# Schematic_st500E.net
KiCad netlist of a schematic drawn in Altium Designer
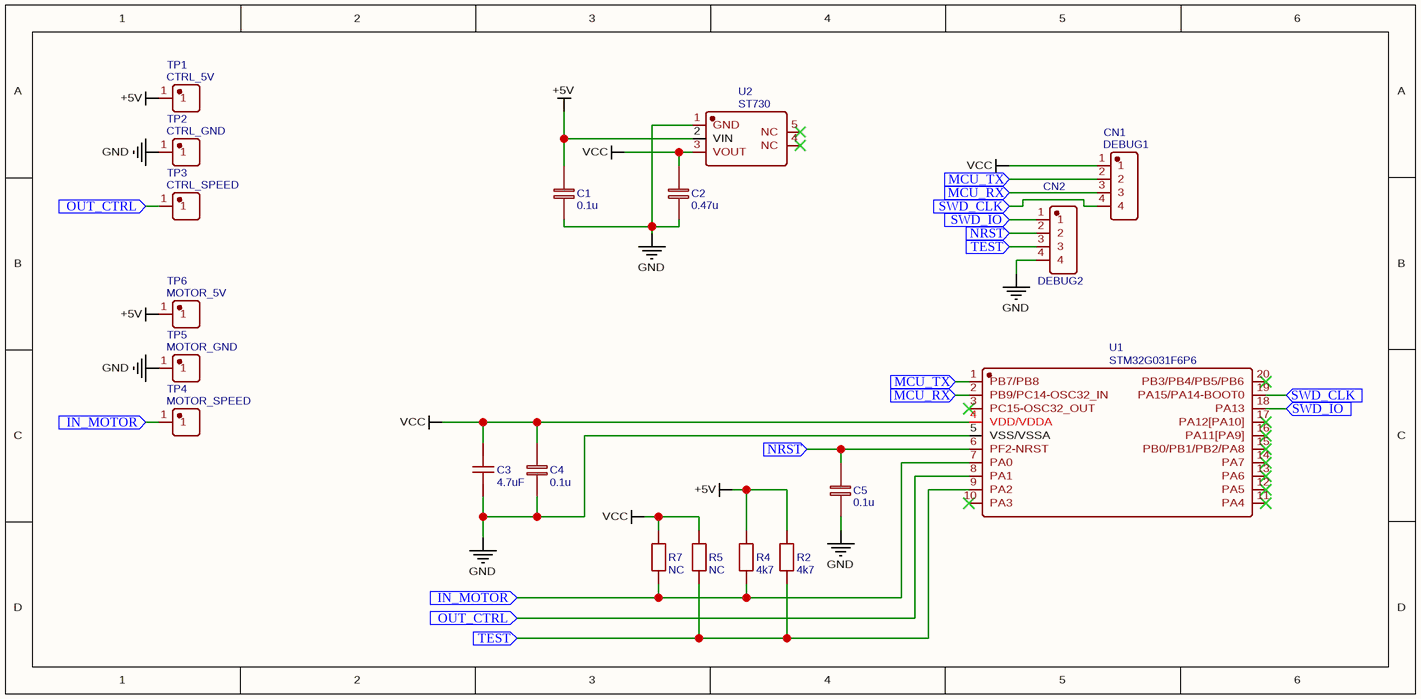
[diagram p0: Schematic_st500E.schdoc]

(export (version "E")
  (design (tool "Eeschema 10.0.6"))
  (components
    (comp (ref "C1")
      (value "0.1u")
      (fields (field (name "CONTRIBUTOR") "LCEDA_Lib"))
      (libsource (lib "altium-import") (part "root_1_0.1u_"))
    )
    (comp (ref "C2")
      (value "0.47u")
      (fields (field (name "CONTRIBUTOR") "LCEDA_Lib"))
      (libsource (lib "altium-import") (part "root_1_0.47u_"))
    )
    (comp (ref "C3")
      (value "4.7uF")
      (fields
        (field (name "BOM_SUPPLIER PART") "C597548")
        (field (name "BOM_MANUFACTURER PART") "1206YG475ZAT2A")
        (field (name "CONTRIBUTOR") "LCSC")
      )
      (libsource (lib "altium-import") (part "root_1_4.7uF_"))
    )
    (comp (ref "C4")
      (value "0.1u")
      (fields (field (name "CONTRIBUTOR") "LCEDA_Lib"))
      (libsource (lib "altium-import") (part "root_1_0.1u_"))
    )
    (comp (ref "C5")
      (value "0.1u")
      (fields (field (name "CONTRIBUTOR") "LCEDA_Lib"))
      (libsource (lib "altium-import") (part "root_1_0.1u_"))
    )
    (comp (ref "CN1")
      (value "DEBUG1")
      (fields
        (field (name "BOM_SUPPLIER PART") "C721862")
        (field (name "BOM_MANUFACTURER PART") "1125-1104G0Z135CR01")
        (field (name "CONTRIBUTOR") "LCSC")
      )
      (libsource (lib "altium-import") (part "root_0_DEBUG1_"))
    )
    (comp (ref "CN2")
      (value "DEBUG2")
      (fields
        (field (name "BOM_SUPPLIER PART") "C721862")
        (field (name "BOM_MANUFACTURER PART") "1125-1104G0Z135CR01")
        (field (name "CONTRIBUTOR") "LCSC")
      )
      (libsource (lib "altium-import") (part "root_0_DEBUG2_"))
    )
    (comp (ref "R2")
      (value "4k7")
      (fields (field (name "CONTRIBUTOR") "LCEDA_Lib"))
      (libsource (lib "altium-import") (part "root_1_4k7_"))
    )
    (comp (ref "R4")
      (value "4k7")
      (fields (field (name "CONTRIBUTOR") "LCEDA_Lib"))
      (libsource (lib "altium-import") (part "root_1_4k7_"))
    )
    (comp (ref "R5")
      (value "NC")
      (fields (field (name "CONTRIBUTOR") "LCEDA_Lib"))
      (libsource (lib "altium-import") (part "root_1_NC_"))
    )
    (comp (ref "R7")
      (value "NC")
      (fields (field (name "CONTRIBUTOR") "LCEDA_Lib"))
      (libsource (lib "altium-import") (part "root_1_NC_"))
    )
    (comp (ref "TP1")
      (value "CTRL_5V")
      (fields
        (field (name "BOM_SUPPLIER PART") "C9900019498")
        (field (name "BOM_MANUFACTURER PART") "RCU-0C")
        (field (name "CONTRIBUTOR") "lcsc")
      )
      (libsource (lib "altium-import") (part "root_0_CTRL_5V_"))
    )
    (comp (ref "TP2")
      (value "CTRL_GND")
      (fields
        (field (name "BOM_SUPPLIER PART") "C9900019498")
        (field (name "BOM_MANUFACTURER PART") "RCU-0C")
        (field (name "CONTRIBUTOR") "lcsc")
      )
      (libsource (lib "altium-import") (part "root_0_CTRL_GND_"))
    )
    (comp (ref "TP3")
      (value "CTRL_SPEED")
      (fields
        (field (name "BOM_SUPPLIER PART") "C9900019498")
        (field (name "BOM_MANUFACTURER PART") "RCU-0C")
        (field (name "CONTRIBUTOR") "lcsc")
      )
      (libsource (lib "altium-import") (part "root_0_CTRL_SPEED_"))
    )
    (comp (ref "TP4")
      (value "MOTOR_SPEED")
      (fields
        (field (name "BOM_SUPPLIER PART") "C9900019498")
        (field (name "BOM_MANUFACTURER PART") "RCU-0C")
        (field (name "CONTRIBUTOR") "lcsc")
      )
      (libsource (lib "altium-import") (part "root_0_MOTOR_SPEED_"))
    )
    (comp (ref "TP5")
      (value "MOTOR_GND")
      (fields
        (field (name "BOM_SUPPLIER PART") "C9900019498")
        (field (name "BOM_MANUFACTURER PART") "RCU-0C")
        (field (name "CONTRIBUTOR") "lcsc")
      )
      (libsource (lib "altium-import") (part "root_0_MOTOR_GND_"))
    )
    (comp (ref "TP6")
      (value "MOTOR_5V")
      (fields
        (field (name "BOM_SUPPLIER PART") "C9900019498")
        (field (name "BOM_MANUFACTURER PART") "RCU-0C")
        (field (name "CONTRIBUTOR") "lcsc")
      )
      (libsource (lib "altium-import") (part "root_0_MOTOR_5V_"))
    )
    (comp (ref "U1")
      (value "STM32G031F6P6")
      (fields (field (name "BOM_SUPPLIER PART") "C529333") (field (name "CONTRIBUTOR") "LCSC"))
      (libsource (lib "altium-import") (part "root_0_STM32G031F6P6_"))
    )
    (comp (ref "U2")
      (value "ST730")
      (fields
        (field (name "BOM_SUPPLIER PART") "C9900003457")
        (field (name "BOM_MANUFACTURER PART") "SMDSOT23-5LN6210B332MR-G")
        (field (name "CONTRIBUTOR") "LCSC")
      )
      (libsource (lib "altium-import") (part "root_0_ST730_"))
    )
  )
  (nets
    (net (code "1") (name "+5V") (class "Default")
      (node (ref "C1") (pin "2") (pinfunction "2_2") (pintype "passive"))
      (node (ref "R2") (pin "2") (pinfunction "2_2") (pintype "passive"))
      (node (ref "R4") (pin "2") (pinfunction "2_2") (pintype "passive"))
      (node (ref "TP1") (pin "1") (pinfunction "1_1") (pintype "passive"))
      (node (ref "TP6") (pin "1") (pinfunction "1_1") (pintype "passive"))
      (node (ref "U2") (pin "2") (pinfunction "VIN_2") (pintype "passive"))
    )
    (net (code "2") (name "/IN_MOTOR") (class "Default")
      (node (ref "R4") (pin "1") (pinfunction "1_1") (pintype "passive"))
      (node (ref "R7") (pin "1") (pinfunction "1_1") (pintype "passive"))
      (node (ref "TP4") (pin "1") (pinfunction "1_1") (pintype "passive"))
      (node (ref "U1") (pin "7") (pinfunction "PA0_7") (pintype "passive"))
    )
    (net (code "3") (name "/MCU_RX") (class "Default")
      (node (ref "CN1") (pin "3") (pinfunction "3_3") (pintype "passive"))
      (node (ref "U1") (pin "2") (pinfunction "PB9/PC14-OSC32_IN_2") (pintype "passive"))
    )
    (net (code "4") (name "/MCU_TX") (class "Default")
      (node (ref "CN1") (pin "2") (pinfunction "2_2") (pintype "passive"))
      (node (ref "U1") (pin "1") (pinfunction "PB7/PB8_1") (pintype "passive"))
    )
    (net (code "5") (name "/NRST") (class "Default")
      (node (ref "C5") (pin "2") (pinfunction "2_2") (pintype "passive"))
      (node (ref "CN2") (pin "2") (pinfunction "2_2") (pintype "passive"))
      (node (ref "U1") (pin "6") (pinfunction "PF2-NRST_6") (pintype "passive"))
    )
    (net (code "6") (name "/OUT_CTRL") (class "Default")
      (node (ref "TP3") (pin "1") (pinfunction "1_1") (pintype "passive"))
      (node (ref "U1") (pin "8") (pinfunction "PA1_8") (pintype "passive"))
    )
    (net (code "7") (name "/SWD_CLK") (class "Default")
      (node (ref "CN1") (pin "4") (pinfunction "4_4") (pintype "passive"))
      (node (ref "U1") (pin "19") (pinfunction "PA15/PA14-BOOT0_19") (pintype "passive"))
    )
    (net (code "8") (name "/SWD_IO") (class "Default")
      (node (ref "CN2") (pin "1") (pinfunction "1_1") (pintype "passive"))
      (node (ref "U1") (pin "18") (pinfunction "PA13_18") (pintype "passive"))
    )
    (net (code "9") (name "/TEST") (class "Default")
      (node (ref "CN2") (pin "3") (pinfunction "3_3") (pintype "passive"))
      (node (ref "R2") (pin "1") (pinfunction "1_1") (pintype "passive"))
      (node (ref "R5") (pin "1") (pinfunction "1_1") (pintype "passive"))
      (node (ref "U1") (pin "9") (pinfunction "PA2_9") (pintype "passive"))
    )
    (net (code "10") (name "GND") (class "Default")
      (node (ref "C1") (pin "1") (pinfunction "1_1") (pintype "passive"))
      (node (ref "C2") (pin "1") (pinfunction "1_1") (pintype "passive"))
      (node (ref "C3") (pin "1") (pinfunction "1_1") (pintype "passive"))
      (node (ref "C4") (pin "1") (pinfunction "1_1") (pintype "passive"))
      (node (ref "C5") (pin "1") (pinfunction "1_1") (pintype "passive"))
      (node (ref "CN2") (pin "4") (pinfunction "4_4") (pintype "passive"))
      (node (ref "TP2") (pin "1") (pinfunction "1_1") (pintype "passive"))
      (node (ref "TP5") (pin "1") (pinfunction "1_1") (pintype "passive"))
      (node (ref "U1") (pin "5") (pinfunction "VSS/VSSA_5") (pintype "passive"))
      (node (ref "U2") (pin "1") (pinfunction "GND_1") (pintype "passive"))
    )
    (net (code "11") (name "VCC") (class "Default")
      (node (ref "C2") (pin "2") (pinfunction "2_2") (pintype "passive"))
      (node (ref "C3") (pin "2") (pinfunction "2_2") (pintype "passive"))
      (node (ref "C4") (pin "2") (pinfunction "2_2") (pintype "passive"))
      (node (ref "CN1") (pin "1") (pinfunction "1_1") (pintype "passive"))
      (node (ref "R5") (pin "2") (pinfunction "2_2") (pintype "passive"))
      (node (ref "R7") (pin "2") (pinfunction "2_2") (pintype "passive"))
      (node (ref "U1") (pin "4") (pinfunction "VDD/VDDA_4") (pintype "passive"))
      (node (ref "U2") (pin "3") (pinfunction "VOUT_3") (pintype "passive"))
    )
    (net (code "12") (name "unconnected-(U1-PA3-Pad10)") (class "Default")
      (node (ref "U1") (pin "10") (pinfunction "PA3_10") (pintype "passive+no_connect"))
    )
    (net (code "13") (name "unconnected-(U1-PA4-Pad11)") (class "Default")
      (node (ref "U1") (pin "11") (pinfunction "PA4_11") (pintype "passive+no_connect"))
    )
    (net (code "14") (name "unconnected-(U1-PA5-Pad12)") (class "Default")
      (node (ref "U1") (pin "12") (pinfunction "PA5_12") (pintype "passive+no_connect"))
    )
    (net (code "15") (name "unconnected-(U1-PA6-Pad13)") (class "Default")
      (node (ref "U1") (pin "13") (pinfunction "PA6_13") (pintype "passive+no_connect"))
    )
    (net (code "16") (name "unconnected-(U1-PA7-Pad14)") (class "Default")
      (node (ref "U1") (pin "14") (pinfunction "PA7_14") (pintype "passive+no_connect"))
    )
    (net (code "17") (name "unconnected-(U1-PA11[PA9]-Pad16)") (class "Default")
      (node (ref "U1") (pin "16") (pinfunction "PA11[PA9]_16") (pintype "passive+no_connect"))
    )
    (net (code "18") (name "unconnected-(U1-PA12[PA10]-Pad17)") (class "Default")
      (node (ref "U1") (pin "17") (pinfunction "PA12[PA10]_17") (pintype "passive+no_connect"))
    )
    (net (code "19") (name "unconnected-(U1-PB0{slash}PB1{slash}PB2{slash}PA8-Pad15)") (class "Default")
      (node (ref "U1") (pin "15") (pinfunction "PB0/PB1/PB2/PA8_15") (pintype "passive+no_connect"))
    )
    (net (code "20") (name "unconnected-(U1-PB3{slash}PB4{slash}PB5{slash}PB6-Pad20)") (class "Default")
      (node (ref "U1") (pin "20") (pinfunction "PB3/PB4/PB5/PB6_20") (pintype "passive+no_connect"))
    )
    (net (code "21") (name "unconnected-(U1-PC15-OSC32_OUT-Pad3)") (class "Default")
      (node (ref "U1") (pin "3") (pinfunction "PC15-OSC32_OUT_3") (pintype "passive+no_connect"))
    )
    (net (code "22") (name "unconnected-(U2-NC-Pad4)") (class "Default")
      (node (ref "U2") (pin "4") (pinfunction "NC_4") (pintype "passive+no_connect"))
    )
    (net (code "23") (name "unconnected-(U2-NC-Pad5)") (class "Default")
      (node (ref "U2") (pin "5") (pinfunction "NC_5") (pintype "passive+no_connect"))
    )
  )
)
